# GSM.net
KiCad netlist of a schematic drawn in Altium Designer
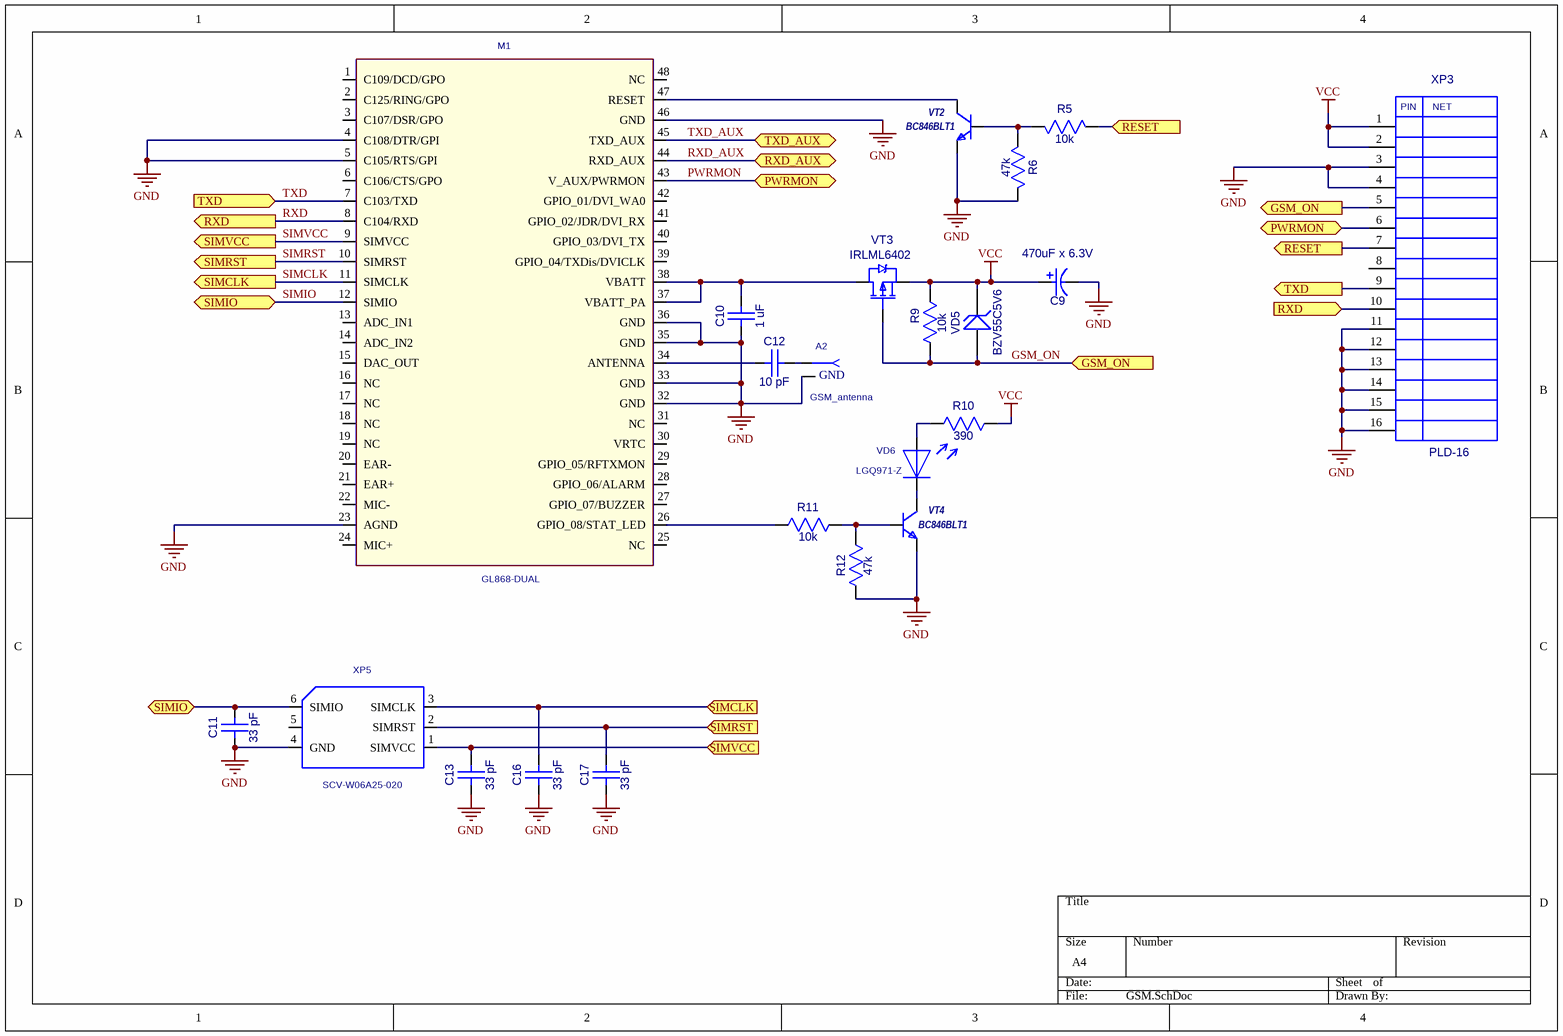
[diagram p0: GSM.SchDoc]

(export (version "E")
  (design (tool "Eeschema 10.0.6"))
  (components
    (comp (ref "A2")
      (value "GSM_antenna")
      (footprint "GSM_antenna_pad")
      (description "GSM_antenna_pad")
      (libsource (lib "gprs_modem") (part "GSM_antenna_pad"))
    )
    (comp (ref "C9")
      (value "470uF x 6.3V")
      (footprint "TAJ-D-1M")
      (description "TAJ-D")
      (libsource (lib "gprs_modem") (part "TAJ-D"))
    )
    (comp (ref "C10")
      (value "1 uF")
      (footprint "CC0603-3M")
      (description "CC0603")
      (libsource (lib "gprs_modem") (part "CC0603"))
    )
    (comp (ref "C11")
      (value "33 pF")
      (footprint "CC0603-3M")
      (description "CC0603")
      (libsource (lib "*") (part "CC0603"))
    )
    (comp (ref "C12")
      (value "10 pF")
      (footprint "CC0603-3M")
      (description "CC0603")
      (libsource (lib "*") (part "CC0603"))
    )
    (comp (ref "C13")
      (value "33 pF")
      (footprint "CC0603-3M")
      (description "CC0603")
      (libsource (lib "*") (part "CC0603"))
    )
    (comp (ref "C16")
      (value "33 pF")
      (footprint "CC0603-3M")
      (description "CC0603")
      (libsource (lib "*") (part "CC0603"))
    )
    (comp (ref "C17")
      (value "33 pF")
      (footprint "CC0603-3M")
      (description "CC0603")
      (libsource (lib "*") (part "CC0603"))
    )
    (comp (ref "M1")
      (value "GL868-DUAL")
      (footprint "GL868-DUAL")
      (libsource (lib "gprs_modem") (part "GL868-DUAL"))
    )
    (comp (ref "R5")
      (value "10k")
      (footprint "RC0603-3M")
      (description "RC0603")
      (libsource (lib "gprs_modem") (part "RC0603"))
    )
    (comp (ref "R6")
      (value "47k")
      (footprint "RC0603-3M")
      (description "RC0603")
      (libsource (lib "gprs_modem") (part "RC0603"))
    )
    (comp (ref "R9")
      (value "10k")
      (footprint "RC0603-3M")
      (description "RC0603")
      (libsource (lib "*") (part "RC0603"))
    )
    (comp (ref "R10")
      (value "390")
      (footprint "RC0603-3M")
      (description "RC0603")
      (libsource (lib "gprs_modem") (part "RC0603"))
    )
    (comp (ref "R11")
      (value "10k")
      (footprint "RC0603-3M")
      (description "RC0603")
      (libsource (lib "gprs_modem") (part "RC0603"))
    )
    (comp (ref "R12")
      (value "47k")
      (footprint "RC0603-3M")
      (description "RC0603")
      (libsource (lib "gprs_modem") (part "RC0603"))
    )
    (comp (ref "VD5")
      (value "BZV55C5V6")
      (footprint "SOD80")
      (description "Zener Voltage Regulator Diode")
      (libsource (lib "gprs_modem") (part "BZV55C5V1"))
    )
    (comp (ref "VD6")
      (value "LGQ971-Z")
      (footprint "LED0603")
      (description "LED_0603")
      (libsource (lib "gprs_modem") (part "LED_0603"))
    )
    (comp (ref "VT2")
      (value "BC846BLT1")
      (footprint "SOT-23(123)")
      (libsource (lib "gprs_modem") (part "BC846BLT1"))
    )
    (comp (ref "VT3")
      (value "IRLML6402")
      (footprint "SOT-23(123)")
      (description "HEXFET Power MOSFET")
      (libsource (lib "gprs_modem") (part "IRLML6402"))
    )
    (comp (ref "VT4")
      (value "BC846BLT1")
      (footprint "SOT-23(123)")
      (libsource (lib "gprs_modem") (part "BC846BLT1"))
    )
    (comp (ref "XP3") (value "PLD-16") (footprint "PIN16") (libsource (lib "gprs_modem") (part "PLD-16")))
    (comp (ref "XP5")
      (value "SCV-W06A25-020")
      (footprint "SCVW06A25020")
      (libsource (lib "*") (part "SCV-W06A25-020"))
    )
  )
  (nets
    (net (code "1") (name "/GSM_ON") (class "Default")
      (node (ref "R9") (pin "2") (pinfunction "B_2") (pintype "passive"))
      (node (ref "VD5") (pin "1") (pinfunction "A_1") (pintype "passive"))
      (node (ref "VT3") (pin "1") (pinfunction "G_1") (pintype "passive"))
      (node (ref "XP3") (pin "5") (pinfunction "5_5") (pintype "passive"))
    )
    (net (code "2") (name "/PWRMON") (class "Default")
      (node (ref "M1") (pin "43") (pinfunction "V_AUX/PWRMON_43") (pintype "passive"))
      (node (ref "XP3") (pin "6") (pinfunction "6_6") (pintype "passive"))
    )
    (net (code "3") (name "/RESET") (class "Default")
      (node (ref "R5") (pin "1") (pinfunction "A_1") (pintype "passive"))
      (node (ref "XP3") (pin "7") (pinfunction "7_7") (pintype "passive"))
    )
    (net (code "4") (name "/RXD") (class "Default")
      (node (ref "M1") (pin "8") (pinfunction "C104/RXD_8") (pintype "passive"))
      (node (ref "XP3") (pin "10") (pinfunction "10_10") (pintype "passive"))
    )
    (net (code "5") (name "/RXD_AUX") (class "Default")
      (node (ref "M1") (pin "44") (pinfunction "RXD_AUX_44") (pintype "passive"))
    )
    (net (code "6") (name "/SIMCLK") (class "Default")
      (node (ref "C16") (pin "2") (pinfunction "B_2") (pintype "passive"))
      (node (ref "M1") (pin "11") (pinfunction "SIMCLK_11") (pintype "passive"))
      (node (ref "XP5") (pin "3") (pinfunction "SIMCLK_3") (pintype "passive"))
    )
    (net (code "7") (name "/SIMIO") (class "Default")
      (node (ref "C11") (pin "2") (pinfunction "B_2") (pintype "passive"))
      (node (ref "M1") (pin "12") (pinfunction "SIMIO_12") (pintype "passive"))
      (node (ref "XP5") (pin "6") (pinfunction "SIMIO_6") (pintype "passive"))
    )
    (net (code "8") (name "/SIMRST") (class "Default")
      (node (ref "C17") (pin "2") (pinfunction "B_2") (pintype "passive"))
      (node (ref "M1") (pin "10") (pinfunction "SIMRST_10") (pintype "passive"))
      (node (ref "XP5") (pin "2") (pinfunction "SIMRST_2") (pintype "passive"))
    )
    (net (code "9") (name "/SIMVCC") (class "Default")
      (node (ref "C13") (pin "2") (pinfunction "B_2") (pintype "passive"))
      (node (ref "M1") (pin "9") (pinfunction "SIMVCC_9") (pintype "passive"))
      (node (ref "XP5") (pin "1") (pinfunction "SIMVCC_1") (pintype "passive"))
    )
    (net (code "10") (name "/TXD") (class "Default")
      (node (ref "M1") (pin "7") (pinfunction "C103/TXD_7") (pintype "passive"))
      (node (ref "XP3") (pin "9") (pinfunction "9_9") (pintype "passive"))
    )
    (net (code "11") (name "/TXD_AUX") (class "Default")
      (node (ref "M1") (pin "45") (pinfunction "TXD_AUX_45") (pintype "passive"))
    )
    (net (code "12") (name "GND") (class "Default")
      (node (ref "A2") (pin "2") (pintype "passive"))
      (node (ref "C10") (pin "1") (pinfunction "A_1") (pintype "passive"))
      (node (ref "C11") (pin "1") (pinfunction "A_1") (pintype "passive"))
      (node (ref "C13") (pin "1") (pinfunction "A_1") (pintype "passive"))
      (node (ref "C16") (pin "1") (pinfunction "A_1") (pintype "passive"))
      (node (ref "C17") (pin "1") (pinfunction "A_1") (pintype "passive"))
      (node (ref "C9") (pin "2") (pinfunction "B_2") (pintype "passive"))
      (node (ref "M1") (pin "23") (pinfunction "AGND_23") (pintype "passive"))
      (node (ref "M1") (pin "32") (pinfunction "GND_32") (pintype "passive"))
      (node (ref "M1") (pin "33") (pinfunction "GND_33") (pintype "passive"))
      (node (ref "M1") (pin "35") (pinfunction "GND_35") (pintype "passive"))
      (node (ref "M1") (pin "36") (pinfunction "GND_36") (pintype "passive"))
      (node (ref "M1") (pin "4") (pinfunction "C108/DTR/GPI_4") (pintype "passive"))
      (node (ref "M1") (pin "46") (pinfunction "GND_46") (pintype "passive"))
      (node (ref "M1") (pin "5") (pinfunction "C105/RTS/GPI_5") (pintype "passive"))
      (node (ref "R12") (pin "2") (pinfunction "B_2") (pintype "passive"))
      (node (ref "R6") (pin "2") (pinfunction "B_2") (pintype "passive"))
      (node (ref "VT2") (pin "2") (pinfunction "E_2") (pintype "passive"))
      (node (ref "VT4") (pin "2") (pinfunction "E_2") (pintype "passive"))
      (node (ref "XP3") (pin "11") (pinfunction "11_11") (pintype "passive"))
      (node (ref "XP3") (pin "12") (pinfunction "12_12") (pintype "passive"))
      (node (ref "XP3") (pin "13") (pinfunction "13_13") (pintype "passive"))
      (node (ref "XP3") (pin "14") (pinfunction "14_14") (pintype "passive"))
      (node (ref "XP3") (pin "15") (pinfunction "15_15") (pintype "passive"))
      (node (ref "XP3") (pin "16") (pinfunction "16_16") (pintype "passive"))
      (node (ref "XP3") (pin "3") (pinfunction "3_3") (pintype "passive"))
      (node (ref "XP3") (pin "4") (pinfunction "4_4") (pintype "passive"))
      (node (ref "XP5") (pin "4") (pinfunction "GND_4") (pintype "passive"))
    )
    (net (code "13") (name "Net-(C10-B)") (class "Default")
      (node (ref "C10") (pin "2") (pinfunction "B_2") (pintype "passive"))
      (node (ref "M1") (pin "37") (pinfunction "VBATT_PA_37") (pintype "passive"))
      (node (ref "M1") (pin "38") (pinfunction "VBATT_38") (pintype "passive"))
      (node (ref "VT3") (pin "3") (pinfunction "D_3") (pintype "passive"))
    )
    (net (code "14") (name "Net-(C12-A)") (class "Default")
      (node (ref "C12") (pin "1") (pinfunction "A_1") (pintype "passive"))
      (node (ref "M1") (pin "34") (pinfunction "ANTENNA_34") (pintype "passive"))
    )
    (net (code "15") (name "Net-(C12-B)") (class "Default")
      (node (ref "A2") (pin "1") (pintype "passive"))
      (node (ref "C12") (pin "2") (pinfunction "B_2") (pintype "passive"))
    )
    (net (code "16") (name "Net-(M1-GPIO_08{slash}STAT_LED)") (class "Default")
      (node (ref "M1") (pin "26") (pinfunction "GPIO_08/STAT_LED_26") (pintype "passive"))
      (node (ref "R11") (pin "1") (pinfunction "A_1") (pintype "passive"))
    )
    (net (code "17") (name "Net-(M1-RESET)") (class "Default")
      (node (ref "M1") (pin "47") (pinfunction "RESET_47") (pintype "passive"))
      (node (ref "VT2") (pin "3") (pinfunction "C_3") (pintype "passive"))
    )
    (net (code "18") (name "Net-(R5-B)") (class "Default")
      (node (ref "R5") (pin "2") (pinfunction "B_2") (pintype "passive"))
      (node (ref "R6") (pin "1") (pinfunction "A_1") (pintype "passive"))
      (node (ref "VT2") (pin "1") (pinfunction "B_1") (pintype "passive"))
    )
    (net (code "19") (name "Net-(R10-A)") (class "Default")
      (node (ref "R10") (pin "1") (pinfunction "A_1") (pintype "passive"))
      (node (ref "VD6") (pin "1") (pintype "passive"))
    )
    (net (code "20") (name "Net-(R11-B)") (class "Default")
      (node (ref "R11") (pin "2") (pinfunction "B_2") (pintype "passive"))
      (node (ref "R12") (pin "1") (pinfunction "A_1") (pintype "passive"))
      (node (ref "VT4") (pin "1") (pinfunction "B_1") (pintype "passive"))
    )
    (net (code "21") (name "Net-(VT4-C)") (class "Default")
      (node (ref "VD6") (pin "2") (pintype "passive"))
      (node (ref "VT4") (pin "3") (pinfunction "C_3") (pintype "passive"))
    )
    (net (code "22") (name "VCC") (class "Default")
      (node (ref "C9") (pin "1") (pinfunction "A_1") (pintype "passive"))
      (node (ref "R10") (pin "2") (pinfunction "B_2") (pintype "passive"))
      (node (ref "R9") (pin "1") (pinfunction "A_1") (pintype "passive"))
      (node (ref "VD5") (pin "2") (pintype "passive"))
      (node (ref "VT3") (pin "2") (pinfunction "S_2") (pintype "passive"))
      (node (ref "XP3") (pin "1") (pinfunction "1_1") (pintype "passive"))
      (node (ref "XP3") (pin "2") (pinfunction "2_2") (pintype "passive"))
    )
    (net (code "23") (name "unconnected-(M1-ADC_IN1-Pad13)") (class "Default")
      (node (ref "M1") (pin "13") (pinfunction "ADC_IN1_13") (pintype "passive"))
    )
    (net (code "24") (name "unconnected-(M1-ADC_IN2-Pad14)") (class "Default")
      (node (ref "M1") (pin "14") (pinfunction "ADC_IN2_14") (pintype "passive"))
    )
    (net (code "25") (name "unconnected-(M1-C106{slash}CTS{slash}GPO-Pad6)") (class "Default")
      (node (ref "M1") (pin "6") (pinfunction "C106/CTS/GPO_6") (pintype "passive"))
    )
    (net (code "26") (name "unconnected-(M1-C107{slash}DSR{slash}GPO-Pad3)") (class "Default")
      (node (ref "M1") (pin "3") (pinfunction "C107/DSR/GPO_3") (pintype "passive"))
    )
    (net (code "27") (name "unconnected-(M1-C109{slash}DCD{slash}GPO-Pad1)") (class "Default")
      (node (ref "M1") (pin "1") (pinfunction "C109/DCD/GPO_1") (pintype "passive"))
    )
    (net (code "28") (name "unconnected-(M1-C125{slash}RING{slash}GPO-Pad2)") (class "Default")
      (node (ref "M1") (pin "2") (pinfunction "C125/RING/GPO_2") (pintype "passive"))
    )
    (net (code "29") (name "unconnected-(M1-DAC_OUT-Pad15)") (class "Default")
      (node (ref "M1") (pin "15") (pinfunction "DAC_OUT_15") (pintype "passive"))
    )
    (net (code "30") (name "unconnected-(M1-EAR+-Pad21)") (class "Default")
      (node (ref "M1") (pin "21") (pinfunction "EAR+_21") (pintype "passive"))
    )
    (net (code "31") (name "unconnected-(M1-EAR--Pad20)") (class "Default")
      (node (ref "M1") (pin "20") (pinfunction "EAR-_20") (pintype "passive"))
    )
    (net (code "32") (name "unconnected-(M1-GPIO_01{slash}DVI_WA0-Pad42)") (class "Default")
      (node (ref "M1") (pin "42") (pinfunction "GPIO_01/DVI_WA0_42") (pintype "passive"))
    )
    (net (code "33") (name "unconnected-(M1-GPIO_02{slash}JDR{slash}DVI_RX-Pad41)") (class "Default")
      (node (ref "M1") (pin "41") (pinfunction "GPIO_02/JDR/DVI_RX_41") (pintype "passive"))
    )
    (net (code "34") (name "unconnected-(M1-GPIO_03{slash}DVI_TX-Pad40)") (class "Default")
      (node (ref "M1") (pin "40") (pinfunction "GPIO_03/DVI_TX_40") (pintype "passive"))
    )
    (net (code "35") (name "unconnected-(M1-GPIO_04{slash}TXDis{slash}DVICLK-Pad39)") (class "Default")
      (node (ref "M1") (pin "39") (pinfunction "GPIO_04/TXDis/DVICLK_39") (pintype "passive"))
    )
    (net (code "36") (name "unconnected-(M1-GPIO_05{slash}RFTXMON-Pad29)") (class "Default")
      (node (ref "M1") (pin "29") (pinfunction "GPIO_05/RFTXMON_29") (pintype "passive"))
    )
    (net (code "37") (name "unconnected-(M1-GPIO_06{slash}ALARM-Pad28)") (class "Default")
      (node (ref "M1") (pin "28") (pinfunction "GPIO_06/ALARM_28") (pintype "passive"))
    )
    (net (code "38") (name "unconnected-(M1-GPIO_07{slash}BUZZER-Pad27)") (class "Default")
      (node (ref "M1") (pin "27") (pinfunction "GPIO_07/BUZZER_27") (pintype "passive"))
    )
    (net (code "39") (name "unconnected-(M1-MIC+-Pad24)") (class "Default")
      (node (ref "M1") (pin "24") (pinfunction "MIC+_24") (pintype "passive"))
    )
    (net (code "40") (name "unconnected-(M1-MIC--Pad22)") (class "Default")
      (node (ref "M1") (pin "22") (pinfunction "MIC-_22") (pintype "passive"))
    )
    (net (code "41") (name "unconnected-(M1-NC-Pad16)") (class "Default")
      (node (ref "M1") (pin "16") (pinfunction "NC_16") (pintype "passive"))
    )
    (net (code "42") (name "unconnected-(M1-NC-Pad17)") (class "Default")
      (node (ref "M1") (pin "17") (pinfunction "NC_17") (pintype "passive"))
    )
    (net (code "43") (name "unconnected-(M1-NC-Pad18)") (class "Default")
      (node (ref "M1") (pin "18") (pinfunction "NC_18") (pintype "passive"))
    )
    (net (code "44") (name "unconnected-(M1-NC-Pad19)") (class "Default")
      (node (ref "M1") (pin "19") (pinfunction "NC_19") (pintype "passive"))
    )
    (net (code "45") (name "unconnected-(M1-NC-Pad25)") (class "Default")
      (node (ref "M1") (pin "25") (pinfunction "NC_25") (pintype "passive"))
    )
    (net (code "46") (name "unconnected-(M1-NC-Pad31)") (class "Default")
      (node (ref "M1") (pin "31") (pinfunction "NC_31") (pintype "passive"))
    )
    (net (code "47") (name "unconnected-(M1-NC-Pad48)") (class "Default")
      (node (ref "M1") (pin "48") (pinfunction "NC_48") (pintype "passive"))
    )
    (net (code "48") (name "unconnected-(M1-VRTC-Pad30)") (class "Default")
      (node (ref "M1") (pin "30") (pinfunction "VRTC_30") (pintype "passive"))
    )
    (net (code "49") (name "unconnected-(XP3-Pad8)") (class "Default")
      (node (ref "XP3") (pin "8") (pinfunction "8_8") (pintype "passive"))
    )
    (net (code "50") (name "unconnected-(XP5-Pad5)") (class "Default")
      (node (ref "XP5") (pin "5") (pintype "passive"))
    )
  )
)
